# scheme.net
KiCad netlist of a schematic drawn in Altium Designer
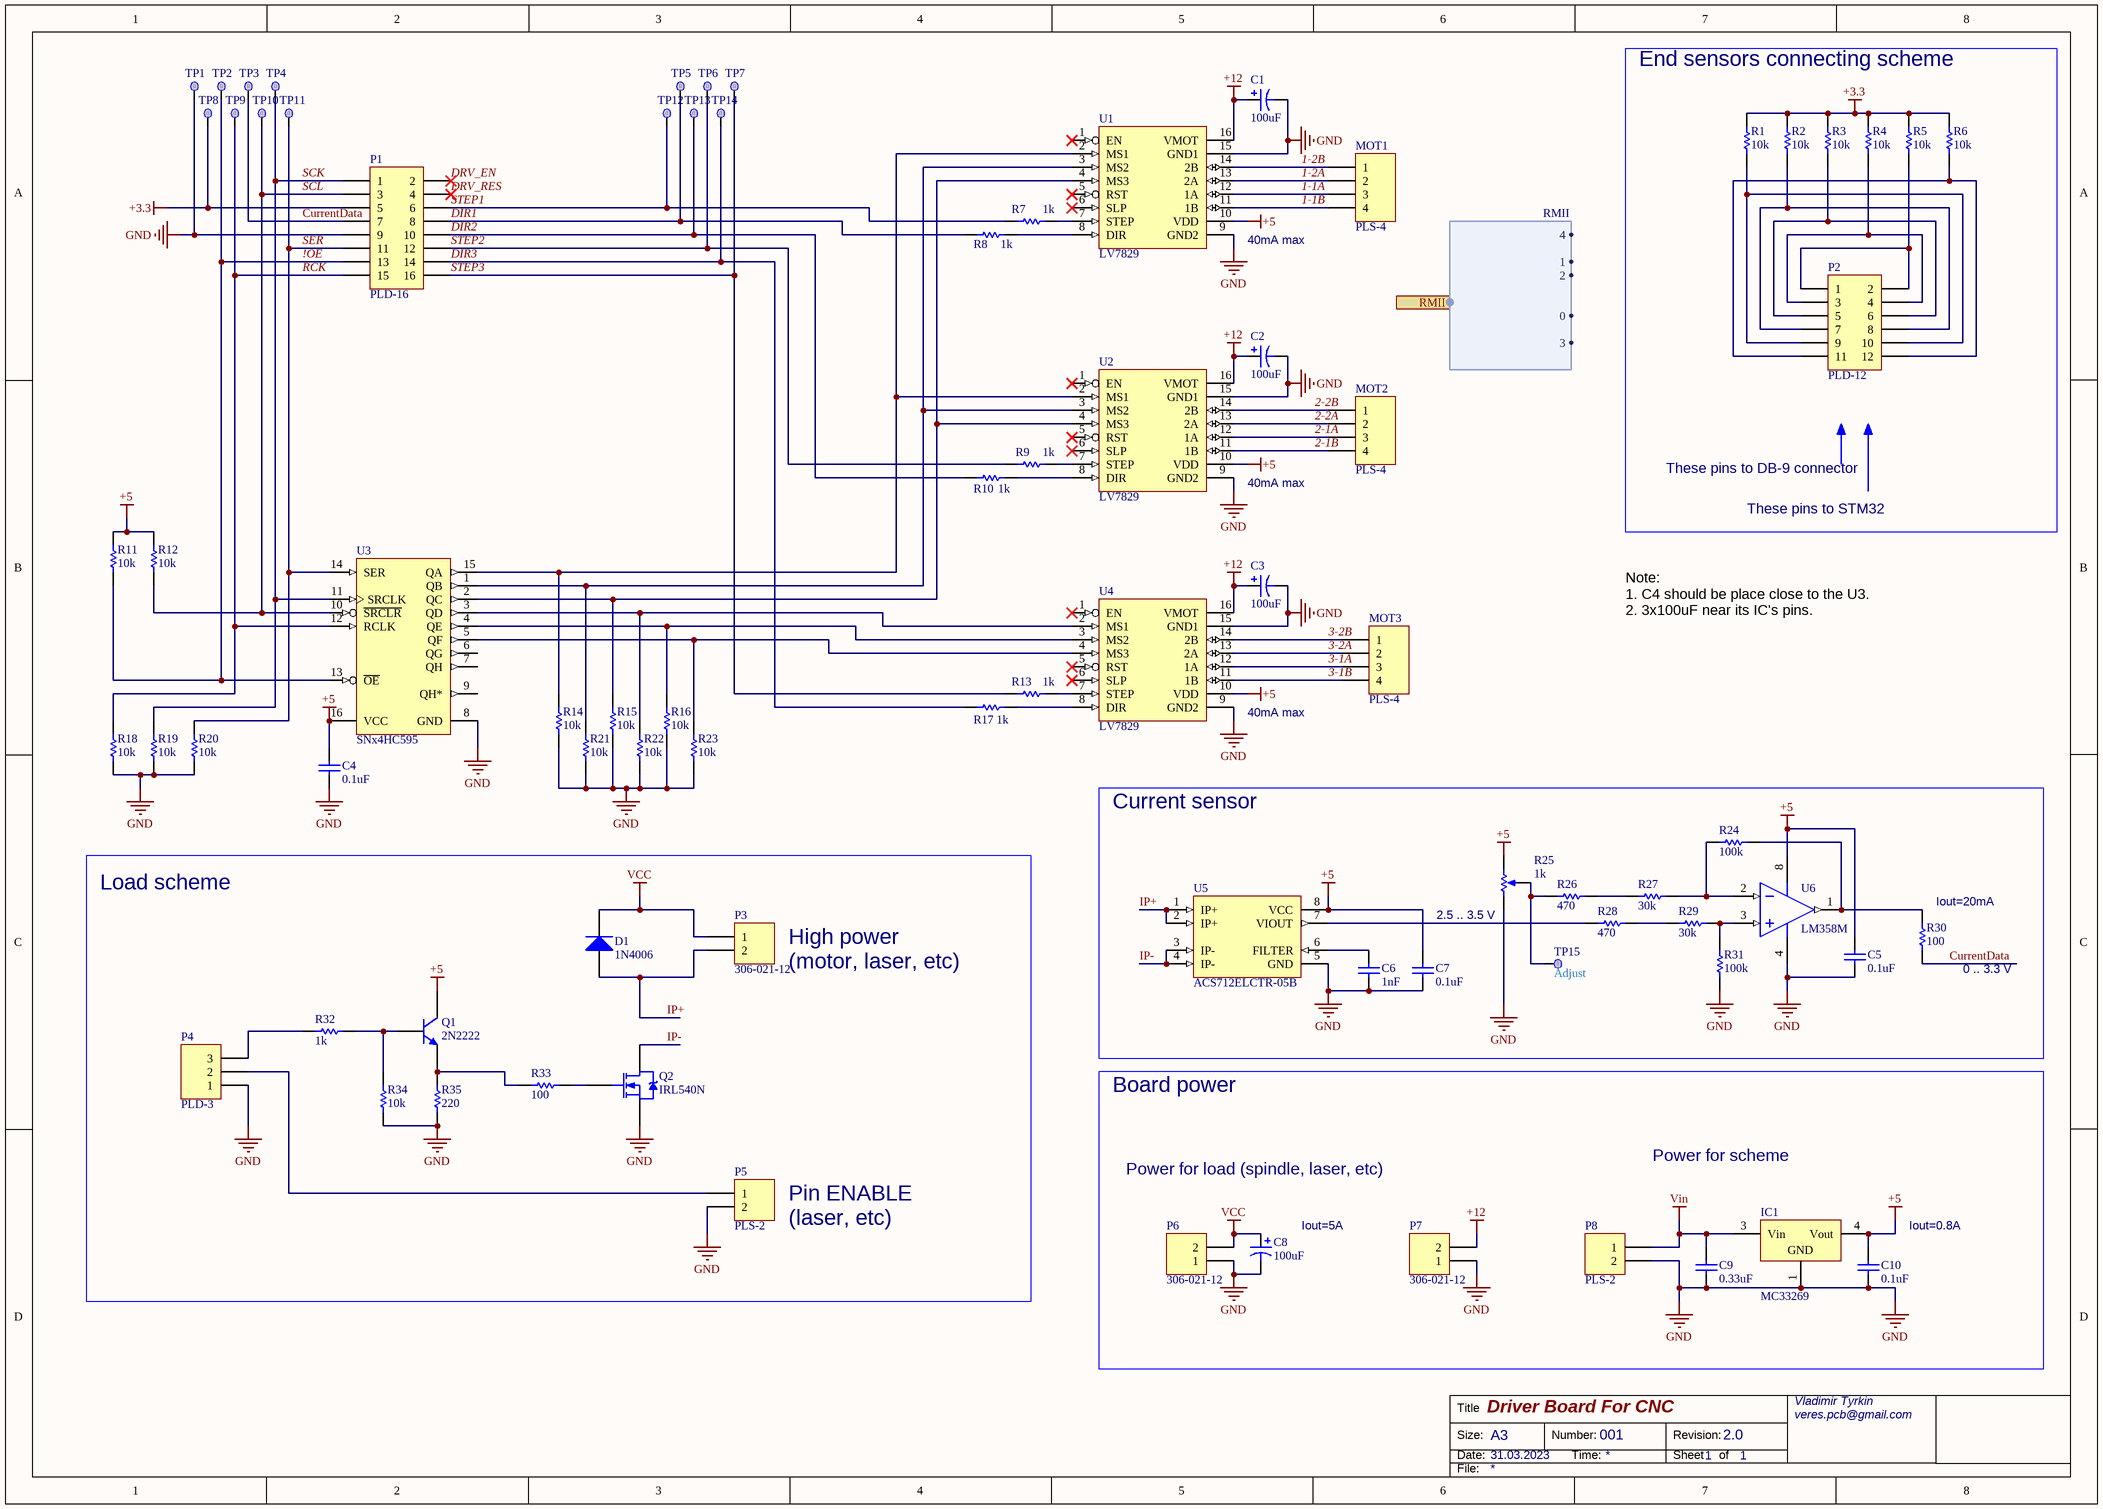
[diagram p0: scheme.SchDoc]

(export (version "E")
  (design (tool "Eeschema 10.0.6"))
  (components
    (comp (ref "C1")
      (value "100uF")
      (footprint "UD-6,3X5,8_NICHICON")
      (description "Polarized Capacitor (Radial) 16V, 105°C, 20% 6.3x5.4mm")
      (fields (field (name "MANUFACTURER") "JB") (field (name "MANUFACTURER_PART_NUMBER") "JCL1C101M063054"))
      (libsource (lib "DriverBoardForCNC") (part "Cap Pol1"))
    )
    (comp (ref "C2")
      (value "100uF")
      (footprint "UD-6,3X5,8_NICHICON")
      (description "Polarized Capacitor (Radial) 16V, 105°C, 20% 6.3x5.4mm")
      (fields (field (name "MANUFACTURER") "JB") (field (name "MANUFACTURER_PART_NUMBER") "JCL1C101M063054"))
      (libsource (lib "DriverBoardForCNC") (part "Cap Pol1"))
    )
    (comp (ref "C3")
      (value "100uF")
      (footprint "UD-6,3X5,8_NICHICON")
      (description "Polarized Capacitor (Radial) 16V, 105°C, 20% 6.3x5.4mm")
      (fields (field (name "MANUFACTURER") "JB") (field (name "MANUFACTURER_PART_NUMBER") "JCL1C101M063054"))
      (libsource (lib "DriverBoardForCNC") (part "Cap Pol1"))
    )
    (comp (ref "C4")
      (value "0.1uF")
      (footprint "C1206")
      (description "Capacitor ceramic SMD")
      (fields
        (field (name "MANUFACTURER") "Murata")
        (field (name "MANUFACTURER_PART_NUMBER") "GRM319R71H104K")
      )
      (libsource (lib "DriverBoardForCNC") (part "Cap"))
    )
    (comp (ref "C5")
      (value "0.1uF")
      (footprint "C1206")
      (description "Capacitor ceramic SMD")
      (fields
        (field (name "MANUFACTURER") "Murata")
        (field (name "MANUFACTURER_PART_NUMBER") "GRM319R71H104K")
      )
      (libsource (lib "DriverBoardForCNC") (part "Cap"))
    )
    (comp (ref "C6")
      (value "1nF")
      (footprint "C0805")
      (description "Capacitor ceramic SMD")
      (fields
        (field (name "MANUFACTURER") "HOLYSTONECAPS")
        (field (name "MANUFACTURER_PART_NUMBER") "MLCC1000pFX7R50V10%0805")
      )
      (libsource (lib "DriverBoardForCNC") (part "Cap"))
    )
    (comp (ref "C7")
      (value "0.1uF")
      (footprint "C1206")
      (description "Capacitor ceramic SMD")
      (fields
        (field (name "MANUFACTURER") "Murata")
        (field (name "MANUFACTURER_PART_NUMBER") "GRM319R71H104K")
      )
      (libsource (lib "DriverBoardForCNC") (part "Cap"))
    )
    (comp (ref "C8")
      (value "100uF")
      (footprint "UD-6,3X5,8_NICHICON")
      (description "Polarized Capacitor (Radial) 16V, 105°C, 20% 6.3x5.4mm")
      (fields (field (name "MANUFACTURER") "JB") (field (name "MANUFACTURER_PART_NUMBER") "JCL1C101M063054"))
      (libsource (lib "DriverBoardForCNC") (part "Cap Pol1"))
    )
    (comp (ref "C9")
      (value "0.33uF")
      (footprint "C1206")
      (description "Capacitor ceramic SMD")
      (fields
        (field (name "MANUFACTURER") "Murata")
        (field (name "MANUFACTURER_PART_NUMBER") "GRM319R71H334KA01D")
      )
      (libsource (lib "DriverBoardForCNC") (part "Cap"))
    )
    (comp (ref "C10")
      (value "0.1uF")
      (footprint "C1206")
      (description "Capacitor ceramic SMD")
      (fields
        (field (name "MANUFACTURER") "Murata")
        (field (name "MANUFACTURER_PART_NUMBER") "GRM319R71H104K")
      )
      (libsource (lib "DriverBoardForCNC") (part "Cap"))
    )
    (comp (ref "D1")
      (value "1N4006")
      (footprint "DO-41")
      (description "1 Amp General Purpose Rectifier")
      (fields (field (name "MANUFACTURER") "DC COMPONENTS CO., LTD."))
      (libsource (lib "DriverBoardForCNC") (part "Diode 1N4004"))
    )
    (comp (ref "IC1")
      (value "MC33269")
      (footprint "DPAK")
      (description "5V Voltage Regulator")
      (fields
        (field (name "MANUFACTURER_PART_NUMBER") "MC33269DT−5.0")
        (field (name "MANUFACTURER") "ON Semiconductor")
      )
      (libsource (lib "DriverBoardForCNC") (part "Volt Reg 5V"))
    )
    (comp (ref "MOT1")
      (value "PLS-4")
      (footprint "HDR1X4")
      (description "Header, 4-Pin")
      (fields
        (field (name "MANUFACTURER") "Connfly")
        (field (name "MANUFACTURER_PART_NUMBER") "DS1021-1*4SF11-B")
      )
      (libsource (lib "DriverBoardForCNC") (part "Header 4"))
    )
    (comp (ref "MOT2")
      (value "PLS-4")
      (footprint "HDR1X4")
      (description "Header, 4-Pin")
      (fields
        (field (name "MANUFACTURER") "Connfly")
        (field (name "MANUFACTURER_PART_NUMBER") "DS1021-1*4SF11-B")
      )
      (libsource (lib "DriverBoardForCNC") (part "Header 4"))
    )
    (comp (ref "MOT3")
      (value "PLS-4")
      (footprint "HDR1X4")
      (description "Header, 4-Pin")
      (fields
        (field (name "MANUFACTURER") "Connfly")
        (field (name "MANUFACTURER_PART_NUMBER") "DS1021-1*4SF11-B")
      )
      (libsource (lib "DriverBoardForCNC") (part "Header 4"))
    )
    (comp (ref "P1")
      (value "PLD-16")
      (footprint "HDR2X8")
      (description "Header, 8-Pin, Dual row")
      (fields
        (field (name "MANUFACTURER") "Connfly")
        (field (name "MANUFACTURER_PART_NUMBER") "DS1021-2*8SF11-B")
      )
      (libsource (lib "DriverBoardForCNC") (part "Header 8X2"))
    )
    (comp (ref "P2")
      (value "PLD-12")
      (footprint "HDR2X6")
      (description "Header, 6-Pin, Dual row")
      (fields
        (field (name "MANUFACTURER") "Connfly")
        (field (name "MANUFACTURER_PART_NUMBER") "DS1021-2*6SF11-B")
      )
      (libsource (lib "DriverBoardForCNC") (part "Header 6X2"))
    )
    (comp (ref "P3")
      (value "306-021-12")
      (footprint "W237-102")
      (description "Screw connector, 2-Pin")
      (fields
        (field (name "MANUFACTURER") "Ningbo Xinya M&E")
        (field (name "MANUFACTURER_PART_NUMBER") "XY306A-5.0-2P-12")
      )
      (libsource (lib "DriverBoardForCNC") (part "Header 2"))
    )
    (comp (ref "P4")
      (value "PLD-3")
      (footprint "HDR1X3")
      (description "Header, 3-Pin")
      (fields
        (field (name "MANUFACTURER") "Connfly")
        (field (name "MANUFACTURER_PART_NUMBER") "DS1021-1*3SF11-B")
      )
      (libsource (lib "DriverBoardForCNC") (part "Header 3"))
    )
    (comp (ref "P5")
      (value "PLS-2")
      (footprint "HDR1X2")
      (description "Header, 2-Pin")
      (fields
        (field (name "MANUFACTURER") "Connfly")
        (field (name "MANUFACTURER_PART_NUMBER") "DS1021-1*2SF11-B")
      )
      (libsource (lib "DriverBoardForCNC") (part "Header 2"))
    )
    (comp (ref "P6")
      (value "306-021-12")
      (footprint "W237-102")
      (description "Screw connector, 2-Pin")
      (fields
        (field (name "MANUFACTURER") "Ningbo Xinya M&E")
        (field (name "MANUFACTURER_PART_NUMBER") "XY306A-5.0-2P-12")
      )
      (libsource (lib "") (part "Header 2_2"))
    )
    (comp (ref "P7")
      (value "306-021-12")
      (footprint "W237-102")
      (description "Screw connector, 2-Pin")
      (fields
        (field (name "MANUFACTURER") "Ningbo Xinya M&E")
        (field (name "MANUFACTURER_PART_NUMBER") "XY306A-5.0-2P-12")
      )
      (libsource (lib "") (part "Header 2_2"))
    )
    (comp (ref "P8")
      (value "PLS-2")
      (footprint "HDR1X2")
      (description "Header, 2-Pin")
      (fields
        (field (name "MANUFACTURER") "Connfly")
        (field (name "MANUFACTURER_PART_NUMBER") "DS1021-1*2SF11-B")
      )
      (libsource (lib "") (part "Header 2_1"))
    )
    (comp (ref "Q1")
      (value "2N2222")
      (footprint "TO92")
      (description "NPN Bipolar Transistor")
      (fields
        (field (name "MANUFACTURER") "ON Semiconductor")
        (field (name "MANUFACTURER_PART_NUMBER") "KSP2222ABU")
      )
      (libsource (lib "DriverBoardForCNC") (part "NPN"))
    )
    (comp (ref "Q2")
      (value "IRL540N")
      (footprint "TO220BV")
      (description "N-Channel Power MOSFET")
      (fields
        (field (name "MANUFACTURER") "Infineon Technologies")
        (field (name "MANUFACTURER_PART_NUMBER") "IRL540NPBF")
      )
      (libsource (lib "DriverBoardForCNC") (part "NMOS-2"))
    )
    (comp (ref "R1")
      (value "10k")
      (footprint "RES-0805")
      (description "Rectangular Thick Film Chip Resistor")
      (fields
        (field (name "MANUFACTURER_PART_NUMBER") "RC0805FR-0710KL")
        (field (name "MANUFACTURER") "Yageo")
      )
      (libsource (lib "DriverBoardForCNC") (part "Res"))
    )
    (comp (ref "R2")
      (value "10k")
      (footprint "RES-0805")
      (description "Rectangular Thick Film Chip Resistor")
      (fields
        (field (name "MANUFACTURER_PART_NUMBER") "RC0805FR-0710KL")
        (field (name "MANUFACTURER") "Yageo")
      )
      (libsource (lib "DriverBoardForCNC") (part "Res"))
    )
    (comp (ref "R3")
      (value "10k")
      (footprint "RES-0805")
      (description "Rectangular Thick Film Chip Resistor")
      (fields
        (field (name "MANUFACTURER_PART_NUMBER") "RC0805FR-0710KL")
        (field (name "MANUFACTURER") "Yageo")
      )
      (libsource (lib "DriverBoardForCNC") (part "Res"))
    )
    (comp (ref "R4")
      (value "10k")
      (footprint "RES-0805")
      (description "Rectangular Thick Film Chip Resistor")
      (fields
        (field (name "MANUFACTURER_PART_NUMBER") "RC0805FR-0710KL")
        (field (name "MANUFACTURER") "Yageo")
      )
      (libsource (lib "DriverBoardForCNC") (part "Res"))
    )
    (comp (ref "R5")
      (value "10k")
      (footprint "RES-0805")
      (description "Rectangular Thick Film Chip Resistor")
      (fields
        (field (name "MANUFACTURER_PART_NUMBER") "RC0805FR-0710KL")
        (field (name "MANUFACTURER") "Yageo")
      )
      (libsource (lib "DriverBoardForCNC") (part "Res"))
    )
    (comp (ref "R6")
      (value "10k")
      (footprint "RES-0805")
      (description "Rectangular Thick Film Chip Resistor")
      (fields
        (field (name "MANUFACTURER_PART_NUMBER") "RC0805FR-0710KL")
        (field (name "MANUFACTURER") "Yageo")
      )
      (libsource (lib "DriverBoardForCNC") (part "Res"))
    )
    (comp (ref "R7")
      (value "1k")
      (footprint "RES-0805")
      (description "Rectangular Thick Film Chip Resistor")
      (fields
        (field (name "MANUFACTURER") "Yageo")
        (field (name "MANUFACTURER_PART_NUMBER") "RC0805FR-071KL")
      )
      (libsource (lib "DriverBoardForCNC") (part "Res"))
    )
    (comp (ref "R8")
      (value "1k")
      (footprint "RES-0805")
      (description "Rectangular Thick Film Chip Resistor")
      (fields
        (field (name "MANUFACTURER") "Yageo")
        (field (name "MANUFACTURER_PART_NUMBER") "RC0805FR-071KL")
      )
      (libsource (lib "DriverBoardForCNC") (part "Res"))
    )
    (comp (ref "R9")
      (value "1k")
      (footprint "RES-0805")
      (description "Rectangular Thick Film Chip Resistor")
      (fields
        (field (name "MANUFACTURER") "Yageo")
        (field (name "MANUFACTURER_PART_NUMBER") "RC0805FR-071KL")
      )
      (libsource (lib "DriverBoardForCNC") (part "Res"))
    )
    (comp (ref "R10")
      (value "1k")
      (footprint "RES-0805")
      (description "Rectangular Thick Film Chip Resistor")
      (fields
        (field (name "MANUFACTURER") "Yageo")
        (field (name "MANUFACTURER_PART_NUMBER") "RC0805FR-071KL")
      )
      (libsource (lib "DriverBoardForCNC") (part "Res"))
    )
    (comp (ref "R11")
      (value "10k")
      (footprint "RES-0805")
      (description "Rectangular Thick Film Chip Resistor")
      (fields
        (field (name "MANUFACTURER_PART_NUMBER") "RC0805FR-0710KL")
        (field (name "MANUFACTURER") "Yageo")
      )
      (libsource (lib "DriverBoardForCNC") (part "Res"))
    )
    (comp (ref "R12")
      (value "10k")
      (footprint "RES-0805")
      (description "Rectangular Thick Film Chip Resistor")
      (fields
        (field (name "MANUFACTURER_PART_NUMBER") "RC0805FR-0710KL")
        (field (name "MANUFACTURER") "Yageo")
      )
      (libsource (lib "DriverBoardForCNC") (part "Res"))
    )
    (comp (ref "R13")
      (value "1k")
      (footprint "RES-0805")
      (description "Rectangular Thick Film Chip Resistor")
      (fields
        (field (name "MANUFACTURER") "Yageo")
        (field (name "MANUFACTURER_PART_NUMBER") "RC0805FR-071KL")
      )
      (libsource (lib "DriverBoardForCNC") (part "Res"))
    )
    (comp (ref "R14")
      (value "10k")
      (footprint "RES-0805")
      (description "Rectangular Thick Film Chip Resistor")
      (fields
        (field (name "MANUFACTURER_PART_NUMBER") "RC0805FR-0710KL")
        (field (name "MANUFACTURER") "Yageo")
      )
      (libsource (lib "DriverBoardForCNC") (part "Res"))
    )
    (comp (ref "R15")
      (value "10k")
      (footprint "RES-0805")
      (description "Rectangular Thick Film Chip Resistor")
      (fields
        (field (name "MANUFACTURER_PART_NUMBER") "RC0805FR-0710KL")
        (field (name "MANUFACTURER") "Yageo")
      )
      (libsource (lib "DriverBoardForCNC") (part "Res"))
    )
    (comp (ref "R16")
      (value "10k")
      (footprint "RES-0805")
      (description "Rectangular Thick Film Chip Resistor")
      (fields
        (field (name "MANUFACTURER_PART_NUMBER") "RC0805FR-0710KL")
        (field (name "MANUFACTURER") "Yageo")
      )
      (libsource (lib "DriverBoardForCNC") (part "Res"))
    )
    (comp (ref "R17")
      (value "1k")
      (footprint "RES-0805")
      (description "Rectangular Thick Film Chip Resistor")
      (fields
        (field (name "MANUFACTURER") "Yageo")
        (field (name "MANUFACTURER_PART_NUMBER") "RC0805FR-071KL")
      )
      (libsource (lib "DriverBoardForCNC") (part "Res"))
    )
    (comp (ref "R18")
      (value "10k")
      (footprint "RES-0805")
      (description "Rectangular Thick Film Chip Resistor")
      (fields
        (field (name "MANUFACTURER_PART_NUMBER") "RC0805FR-0710KL")
        (field (name "MANUFACTURER") "Yageo")
      )
      (libsource (lib "DriverBoardForCNC") (part "Res"))
    )
    (comp (ref "R19")
      (value "10k")
      (footprint "RES-0805")
      (description "Rectangular Thick Film Chip Resistor")
      (fields
        (field (name "MANUFACTURER_PART_NUMBER") "RC0805FR-0710KL")
        (field (name "MANUFACTURER") "Yageo")
      )
      (libsource (lib "DriverBoardForCNC") (part "Res"))
    )
    (comp (ref "R20")
      (value "10k")
      (footprint "RES-0805")
      (description "Rectangular Thick Film Chip Resistor")
      (fields
        (field (name "MANUFACTURER_PART_NUMBER") "RC0805FR-0710KL")
        (field (name "MANUFACTURER") "Yageo")
      )
      (libsource (lib "DriverBoardForCNC") (part "Res"))
    )
    (comp (ref "R21")
      (value "10k")
      (footprint "RES-0805")
      (description "Rectangular Thick Film Chip Resistor")
      (fields
        (field (name "MANUFACTURER_PART_NUMBER") "RC0805FR-0710KL")
        (field (name "MANUFACTURER") "Yageo")
      )
      (libsource (lib "DriverBoardForCNC") (part "Res"))
    )
    (comp (ref "R22")
      (value "10k")
      (footprint "RES-0805")
      (description "Rectangular Thick Film Chip Resistor")
      (fields
        (field (name "MANUFACTURER_PART_NUMBER") "RC0805FR-0710KL")
        (field (name "MANUFACTURER") "Yageo")
      )
      (libsource (lib "DriverBoardForCNC") (part "Res"))
    )
    (comp (ref "R23")
      (value "10k")
      (footprint "RES-0805")
      (description "Rectangular Thick Film Chip Resistor")
      (fields
        (field (name "MANUFACTURER_PART_NUMBER") "RC0805FR-0710KL")
        (field (name "MANUFACTURER") "Yageo")
      )
      (libsource (lib "DriverBoardForCNC") (part "Res"))
    )
    (comp (ref "R24")
      (value "100k")
      (footprint "RES-0805")
      (description "Rectangular Thick Film Chip Resistor")
      (fields
        (field (name "MANUFACTURER_PART_NUMBER") "RC0805FR-07100KL")
        (field (name "MANUFACTURER") "Yageo")
      )
      (libsource (lib "DriverBoardForCNC") (part "Res"))
    )
    (comp (ref "R25")
      (value "1k")
      (footprint "VR5")
      (description "Potentiometer")
      (fields
        (field (name "MANUFACTURER_PART_NUMBER") "3296W-1-102LF")
        (field (name "MANUFACTURER") "Bourns")
      )
      (libsource (lib "DriverBoardForCNC") (part "RPot"))
    )
    (comp (ref "R26")
      (value "470")
      (footprint "RES-0805")
      (description "Rectangular Thick Film Chip Resistor")
      (fields
        (field (name "MANUFACTURER_PART_NUMBER") "RC0805FR-07470RL")
        (field (name "MANUFACTURER") "Yageo")
      )
      (libsource (lib "DriverBoardForCNC") (part "Res"))
    )
    (comp (ref "R27")
      (value "30k")
      (footprint "RES-0805")
      (description "Rectangular Thick Film Chip Resistor")
      (fields
        (field (name "MANUFACTURER_PART_NUMBER") "RC0805FR-0730KL")
        (field (name "MANUFACTURER") "Yageo")
      )
      (libsource (lib "DriverBoardForCNC") (part "Res"))
    )
    (comp (ref "R28")
      (value "470")
      (footprint "RES-1206")
      (description "Rectangular Thick Film Chip Resistor")
      (fields
        (field (name "MANUFACTURER_PART_NUMBER") "RC1206FR-07470RL")
        (field (name "MANUFACTURER") "Yageo")
      )
      (libsource (lib "DriverBoardForCNC") (part "Res"))
    )
    (comp (ref "R29")
      (value "30k")
      (footprint "RES-0805")
      (description "Rectangular Thick Film Chip Resistor")
      (fields
        (field (name "MANUFACTURER_PART_NUMBER") "RC0805FR-0730KL")
        (field (name "MANUFACTURER") "Yageo")
      )
      (libsource (lib "DriverBoardForCNC") (part "Res"))
    )
    (comp (ref "R30")
      (value "100")
      (footprint "RES-0805")
      (description "Rectangular Thick Film Chip Resistor")
      (fields
        (field (name "MANUFACTURER_PART_NUMBER") "RC0805FR-07100RL")
        (field (name "MANUFACTURER") "Yageo")
      )
      (libsource (lib "DriverBoardForCNC") (part "Res"))
    )
    (comp (ref "R31")
      (value "100k")
      (footprint "RES-0805")
      (description "Rectangular Thick Film Chip Resistor")
      (fields
        (field (name "MANUFACTURER_PART_NUMBER") "RC0805FR-07100KL")
        (field (name "MANUFACTURER") "Yageo")
      )
      (libsource (lib "DriverBoardForCNC") (part "Res"))
    )
    (comp (ref "R32")
      (value "1k")
      (footprint "RES-0805")
      (description "Rectangular Thick Film Chip Resistor")
      (fields
        (field (name "MANUFACTURER") "Yageo")
        (field (name "MANUFACTURER_PART_NUMBER") "RC0805FR-071KL")
      )
      (libsource (lib "DriverBoardForCNC") (part "Res"))
    )
    (comp (ref "R33")
      (value "100")
      (footprint "RES-0805")
      (description "Rectangular Thick Film Chip Resistor")
      (fields
        (field (name "MANUFACTURER_PART_NUMBER") "RC0805FR-07100RL")
        (field (name "MANUFACTURER") "Yageo")
      )
      (libsource (lib "DriverBoardForCNC") (part "Res"))
    )
    (comp (ref "R34")
      (value "10k")
      (footprint "RES-0805")
      (description "Rectangular Thick Film Chip Resistor")
      (fields
        (field (name "MANUFACTURER_PART_NUMBER") "RC0805FR-0710KL")
        (field (name "MANUFACTURER") "Yageo")
      )
      (libsource (lib "DriverBoardForCNC") (part "Res"))
    )
    (comp (ref "R35")
      (value "220")
      (footprint "RES-0805")
      (description "Rectangular Thick Film Chip Resistor")
      (fields
        (field (name "MANUFACTURER_PART_NUMBER") "RC0805FR-07220RL")
        (field (name "MANUFACTURER") "Yageo")
      )
      (libsource (lib "DriverBoardForCNC") (part "Res"))
    )
    (comp (ref "TP1")
      (value "~")
      (footprint "TP_SMD_1MM")
      (description "Test Point")
      (fields (field (name "MANUFACTURER_PART_NUMBER") "n/a"))
      (libsource (lib "DriverBoardForCNC") (part "Test Point"))
    )
    (comp (ref "TP2")
      (value "~")
      (footprint "TP_SMD_1MM")
      (description "Test Point")
      (fields (field (name "MANUFACTURER_PART_NUMBER") "n/a"))
      (libsource (lib "DriverBoardForCNC") (part "Test Point"))
    )
    (comp (ref "TP3")
      (value "~")
      (footprint "TP_SMD_1MM")
      (description "Test Point")
      (fields (field (name "MANUFACTURER_PART_NUMBER") "n/a"))
      (libsource (lib "DriverBoardForCNC") (part "Test Point"))
    )
    (comp (ref "TP4")
      (value "~")
      (footprint "TP_SMD_1MM")
      (description "Test Point")
      (fields (field (name "MANUFACTURER_PART_NUMBER") "n/a"))
      (libsource (lib "DriverBoardForCNC") (part "Test Point"))
    )
    (comp (ref "TP5")
      (value "~")
      (footprint "TP_SMD_1MM")
      (description "Test Point")
      (fields (field (name "MANUFACTURER_PART_NUMBER") "n/a"))
      (libsource (lib "DriverBoardForCNC") (part "Test Point"))
    )
    (comp (ref "TP6")
      (value "~")
      (footprint "TP_SMD_1MM")
      (description "Test Point")
      (fields (field (name "MANUFACTURER_PART_NUMBER") "n/a"))
      (libsource (lib "DriverBoardForCNC") (part "Test Point"))
    )
    (comp (ref "TP7")
      (value "~")
      (footprint "TP_SMD_1MM")
      (description "Test Point")
      (fields (field (name "MANUFACTURER_PART_NUMBER") "n/a"))
      (libsource (lib "DriverBoardForCNC") (part "Test Point"))
    )
    (comp (ref "TP8")
      (value "~")
      (footprint "TP_SMD_1MM")
      (description "Test Point")
      (fields (field (name "MANUFACTURER_PART_NUMBER") "n/a"))
      (libsource (lib "DriverBoardForCNC") (part "Test Point"))
    )
    (comp (ref "TP9")
      (value "~")
      (footprint "TP_SMD_1MM")
      (description "Test Point")
      (fields (field (name "MANUFACTURER_PART_NUMBER") "n/a"))
      (libsource (lib "DriverBoardForCNC") (part "Test Point"))
    )
    (comp (ref "TP10")
      (value "~")
      (footprint "TP_SMD_1MM")
      (description "Test Point")
      (fields (field (name "MANUFACTURER_PART_NUMBER") "n/a"))
      (libsource (lib "DriverBoardForCNC") (part "Test Point"))
    )
    (comp (ref "TP11")
      (value "~")
      (footprint "TP_SMD_1MM")
      (description "Test Point")
      (fields (field (name "MANUFACTURER_PART_NUMBER") "n/a"))
      (libsource (lib "DriverBoardForCNC") (part "Test Point"))
    )
    (comp (ref "TP12")
      (value "~")
      (footprint "TP_SMD_1MM")
      (description "Test Point")
      (fields (field (name "MANUFACTURER_PART_NUMBER") "n/a"))
      (libsource (lib "DriverBoardForCNC") (part "Test Point"))
    )
    (comp (ref "TP13")
      (value "~")
      (footprint "TP_SMD_1MM")
      (description "Test Point")
      (fields (field (name "MANUFACTURER_PART_NUMBER") "n/a"))
      (libsource (lib "DriverBoardForCNC") (part "Test Point"))
    )
    (comp (ref "TP14")
      (value "~")
      (footprint "TP_SMD_1MM")
      (description "Test Point")
      (fields (field (name "MANUFACTURER_PART_NUMBER") "n/a"))
      (libsource (lib "DriverBoardForCNC") (part "Test Point"))
    )
    (comp (ref "TP15")
      (value "Adjust")
      (footprint "TestPoint")
      (description "Test Point")
      (fields (field (name "MANUFACTURER_PART_NUMBER") "n/a"))
      (libsource (lib "") (part "Test Point_1"))
    )
    (comp (ref "U1")
      (value "LV7829")
      (footprint "LV8729_BREAKOUT")
      (description "Stepper motor driver")
      (fields (field (name "MANUFACTURER_PART_NUMBER") "LV7829 Module") (field (name "MANUFACTURER") "China"))
      (libsource (lib "DriverBoardForCNC") (part "LV7829"))
    )
    (comp (ref "U2")
      (value "LV7829")
      (footprint "LV8729_BREAKOUT")
      (description "Stepper motor driver")
      (fields (field (name "MANUFACTURER_PART_NUMBER") "LV7829 Module") (field (name "MANUFACTURER") "China"))
      (libsource (lib "DriverBoardForCNC") (part "LV7829"))
    )
    (comp (ref "U3")
      (value "SNx4HC595")
      (footprint "SO16")
      (description "8-bit shift register with 3-state output register")
      (fields (field (name "MANUFACTURER_PART_NUMBER") "SN74HC595D") (field (name "MANUFACTURER") "TI"))
      (libsource (lib "DriverBoardForCNC") (part "SNx4HC595"))
    )
    (comp (ref "U4")
      (value "LV7829")
      (footprint "LV8729_BREAKOUT")
      (description "Stepper motor driver")
      (fields (field (name "MANUFACTURER_PART_NUMBER") "LV7829 Module") (field (name "MANUFACTURER") "China"))
      (libsource (lib "DriverBoardForCNC") (part "LV7829"))
    )
    (comp (ref "U5")
      (value "ACS712ELCTR-05B")
      (footprint "SO-8_L")
      (description "Hall-Effect-Based Linear Current Sensor +-5A")
      (fields (field (name "MANUFACTURER") "Allegro") (field (name "Comment") "Current Sensor"))
      (libsource (lib "DriverBoardForCNC") (part "ACS712ELCTR-05B"))
    )
    (comp (ref "U6")
      (value "LM358M")
      (footprint "SO-8_L")
      (description "FET Operational Amplifier")
      (fields (field (name "MANUFACTURER_PART_NUMBER") "LM358M/NOPB") (field (name "MANUFACTURER") "TI"))
      (libsource (lib "DriverBoardForCNC") (part "Op Amp"))
    )
  )
  (nets
    (net (code "2") (name "+3.3") (class "Default")
      (node (ref "P1") (pin "5") (pinfunction "5_5") (pintype "passive"))
      (node (ref "R1") (pin "1") (pinfunction "1_1") (pintype "passive"))
      (node (ref "R2") (pin "1") (pinfunction "1_1") (pintype "passive"))
      (node (ref "R3") (pin "1") (pinfunction "1_1") (pintype "passive"))
      (node (ref "R4") (pin "1") (pinfunction "1_1") (pintype "passive"))
      (node (ref "R5") (pin "1") (pinfunction "1_1") (pintype "passive"))
      (node (ref "R6") (pin "1") (pinfunction "1_1") (pintype "passive"))
      (node (ref "TP8") (pin "1") (pinfunction "1_1") (pintype "passive"))
    )
    (net (code "3") (name "+5") (class "Default")
      (node (ref "C10") (pin "2") (pinfunction "2_2") (pintype "passive"))
      (node (ref "C4") (pin "2") (pinfunction "2_2") (pintype "passive"))
      (node (ref "C5") (pin "1") (pinfunction "1_1") (pintype "passive"))
      (node (ref "C7") (pin "2") (pinfunction "2_2") (pintype "passive"))
      (node (ref "IC1") (pin "4") (pinfunction "Vout_4") (pintype "passive"))
      (node (ref "Q1") (pin "1") (pinfunction "C_1") (pintype "passive"))
      (node (ref "R11") (pin "1") (pinfunction "1_1") (pintype "passive"))
      (node (ref "R12") (pin "1") (pinfunction "1_1") (pintype "passive"))
      (node (ref "R25") (pin "3") (pinfunction "BOT_3") (pintype "passive"))
      (node (ref "U1") (pin "10") (pinfunction "VDD_10") (pintype "power_in"))
      (node (ref "U2") (pin "10") (pinfunction "VDD_10") (pintype "power_in"))
      (node (ref "U3") (pin "16") (pinfunction "VCC_16") (pintype "power_in"))
      (node (ref "U4") (pin "10") (pinfunction "VDD_10") (pintype "power_in"))
      (node (ref "U5") (pin "8") (pinfunction "VCC_8") (pintype "power_in"))
      (node (ref "U6") (pin "8") (pinfunction "V+_8") (pintype "power_in"))
    )
    (net (code "4") (name "+12") (class "Default")
      (node (ref "C1") (pin "1") (pinfunction "1_1") (pintype "passive"))
      (node (ref "C2") (pin "1") (pinfunction "1_1") (pintype "passive"))
      (node (ref "C3") (pin "1") (pinfunction "1_1") (pintype "passive"))
      (node (ref "P7") (pin "2") (pinfunction "2_2") (pintype "passive"))
      (node (ref "U1") (pin "16") (pinfunction "VMOT_16") (pintype "power_in"))
      (node (ref "U2") (pin "16") (pinfunction "VMOT_16") (pintype "power_in"))
      (node (ref "U4") (pin "16") (pinfunction "VMOT_16") (pintype "power_in"))
    )
    (net (code "5") (name "/!OE") (class "Default")
      (node (ref "P1") (pin "13") (pinfunction "13_13") (pintype "passive"))
      (node (ref "R11") (pin "2") (pinfunction "2_2") (pintype "passive"))
      (node (ref "TP2") (pin "1") (pinfunction "1_1") (pintype "passive"))
      (node (ref "U3") (pin "13") (pinfunction "~{OE}_13") (pintype "input"))
    )
    (net (code "6") (name "/1-1A") (class "Default")
      (node (ref "MOT1") (pin "3") (pinfunction "3_3") (pintype "passive"))
      (node (ref "U1") (pin "12") (pinfunction "1A_12") (pintype "bidirectional"))
    )
    (net (code "7") (name "/1-1B") (class "Default")
      (node (ref "MOT1") (pin "4") (pinfunction "4_4") (pintype "passive"))
      (node (ref "U1") (pin "11") (pinfunction "1B_11") (pintype "bidirectional"))
    )
    (net (code "8") (name "/1-2A") (class "Default")
      (node (ref "MOT1") (pin "2") (pinfunction "2_2") (pintype "passive"))
      (node (ref "U1") (pin "13") (pinfunction "2A_13") (pintype "bidirectional"))
    )
    (net (code "9") (name "/1-2B") (class "Default")
      (node (ref "MOT1") (pin "1") (pinfunction "1_1") (pintype "passive"))
      (node (ref "U1") (pin "14") (pinfunction "2B_14") (pintype "bidirectional"))
    )
    (net (code "10") (name "/2-1A") (class "Default")
      (node (ref "MOT2") (pin "3") (pinfunction "3_3") (pintype "passive"))
      (node (ref "U2") (pin "12") (pinfunction "1A_12") (pintype "bidirectional"))
    )
    (net (code "11") (name "/2-1B") (class "Default")
      (node (ref "MOT2") (pin "4") (pinfunction "4_4") (pintype "passive"))
      (node (ref "U2") (pin "11") (pinfunction "1B_11") (pintype "bidirectional"))
    )
    (net (code "12") (name "/2-2A") (class "Default")
      (node (ref "MOT2") (pin "2") (pinfunction "2_2") (pintype "passive"))
      (node (ref "U2") (pin "13") (pinfunction "2A_13") (pintype "bidirectional"))
    )
    (net (code "13") (name "/2-2B") (class "Default")
      (node (ref "MOT2") (pin "1") (pinfunction "1_1") (pintype "passive"))
      (node (ref "U2") (pin "14") (pinfunction "2B_14") (pintype "bidirectional"))
    )
    (net (code "14") (name "/3-1A") (class "Default")
      (node (ref "MOT3") (pin "3") (pinfunction "3_3") (pintype "passive"))
      (node (ref "U4") (pin "12") (pinfunction "1A_12") (pintype "bidirectional"))
    )
    (net (code "15") (name "/3-1B") (class "Default")
      (node (ref "MOT3") (pin "4") (pinfunction "4_4") (pintype "passive"))
      (node (ref "U4") (pin "11") (pinfunction "1B_11") (pintype "bidirectional"))
    )
    (net (code "16") (name "/3-2A") (class "Default")
      (node (ref "MOT3") (pin "2") (pinfunction "2_2") (pintype "passive"))
      (node (ref "U4") (pin "13") (pinfunction "2A_13") (pintype "bidirectional"))
    )
    (net (code "17") (name "/3-2B") (class "Default")
      (node (ref "MOT3") (pin "1") (pinfunction "1_1") (pintype "passive"))
      (node (ref "U4") (pin "14") (pinfunction "2B_14") (pintype "bidirectional"))
    )
    (net (code "18") (name "/CurrentData") (class "Default")
      (node (ref "P1") (pin "7") (pinfunction "7_7") (pintype "passive"))
      (node (ref "R30") (pin "2") (pinfunction "2_2") (pintype "passive"))
      (node (ref "TP3") (pin "1") (pinfunction "1_1") (pintype "passive"))
    )
    (net (code "19") (name "/DIR1") (class "Default")
      (node (ref "P1") (pin "8") (pinfunction "8_8") (pintype "passive"))
      (node (ref "R8") (pin "2") (pinfunction "2_2") (pintype "passive"))
      (node (ref "TP5") (pin "1") (pinfunction "1_1") (pintype "passive"))
    )
    (net (code "20") (name "/DIR2") (class "Default")
      (node (ref "P1") (pin "10") (pinfunction "10_10") (pintype "passive"))
      (node (ref "R10") (pin "2") (pinfunction "2_2") (pintype "passive"))
      (node (ref "TP13") (pin "1") (pinfunction "1_1") (pintype "passive"))
    )
    (net (code "21") (name "/DIR3") (class "Default")
      (node (ref "P1") (pin "14") (pinfunction "14_14") (pintype "passive"))
      (node (ref "R17") (pin "2") (pinfunction "2_2") (pintype "passive"))
      (node (ref "TP14") (pin "1") (pinfunction "1_1") (pintype "passive"))
    )
    (net (code "22") (name "/DRV_EN") (class "Default")
      (node (ref "P1") (pin "2") (pinfunction "2_2") (pintype "passive+no_connect"))
    )
    (net (code "23") (name "/DRV_RES") (class "Default")
      (node (ref "P1") (pin "4") (pinfunction "4_4") (pintype "passive+no_connect"))
    )
    (net (code "24") (name "/IP+") (class "Default")
      (node (ref "D1") (pin "1") (pinfunction "A_1") (pintype "passive"))
      (node (ref "P3") (pin "2") (pinfunction "2_2") (pintype "passive"))
      (node (ref "U5") (pin "1") (pinfunction "IP+_1") (pintype "input"))
      (node (ref "U5") (pin "2") (pinfunction "IP+_2") (pintype "input"))
    )
    (net (code "25") (name "/IP-") (class "Default")
      (node (ref "Q2") (pin "2") (pinfunction "D_2") (pintype "passive"))
      (node (ref "U5") (pin "3") (pinfunction "IP-_3") (pintype "input"))
      (node (ref "U5") (pin "4") (pinfunction "IP-_4") (pintype "input"))
    )
    (net (code "26") (name "/RCK") (class "Default")
      (node (ref "P1") (pin "15") (pinfunction "15_15") (pintype "passive"))
      (node (ref "R18") (pin "1") (pinfunction "1_1") (pintype "passive"))
      (node (ref "TP9") (pin "1") (pinfunction "1_1") (pintype "passive"))
      (node (ref "U3") (pin "12") (pinfunction "RCLK_12") (pintype "input"))
    )
    (net (code "27") (name "/SCK") (class "Default")
      (node (ref "P1") (pin "1") (pinfunction "1_1") (pintype "passive"))
      (node (ref "R19") (pin "1") (pinfunction "1_1") (pintype "passive"))
      (node (ref "TP4") (pin "1") (pinfunction "1_1") (pintype "passive"))
      (node (ref "U3") (pin "11") (pinfunction "SRCLK_11") (pintype "input"))
    )
    (net (code "28") (name "/SCL") (class "Default")
      (node (ref "P1") (pin "3") (pinfunction "3_3") (pintype "passive"))
      (node (ref "R12") (pin "2") (pinfunction "2_2") (pintype "passive"))
      (node (ref "TP10") (pin "1") (pinfunction "1_1") (pintype "passive"))
      (node (ref "U3") (pin "10") (pinfunction "~{SRCLR}_10") (pintype "input"))
    )
    (net (code "29") (name "/SER") (class "Default")
      (node (ref "P1") (pin "11") (pinfunction "11_11") (pintype "passive"))
      (node (ref "R20") (pin "1") (pinfunction "1_1") (pintype "passive"))
      (node (ref "TP11") (pin "1") (pinfunction "1_1") (pintype "passive"))
      (node (ref "U3") (pin "14") (pinfunction "SER_14") (pintype "input"))
    )
    (net (code "30") (name "/STEP1") (class "Default")
      (node (ref "P1") (pin "6") (pinfunction "6_6") (pintype "passive"))
      (node (ref "R7") (pin "2") (pinfunction "2_2") (pintype "passive"))
      (node (ref "TP12") (pin "1") (pinfunction "1_1") (pintype "passive"))
    )
    (net (code "31") (name "/STEP2") (class "Default")
      (node (ref "P1") (pin "12") (pinfunction "12_12") (pintype "passive"))
      (node (ref "R9") (pin "2") (pinfunction "2_2") (pintype "passive"))
      (node (ref "TP6") (pin "1") (pinfunction "1_1") (pintype "passive"))
    )
    (net (code "32") (name "/STEP3") (class "Default")
      (node (ref "P1") (pin "16") (pinfunction "16_16") (pintype "passive"))
      (node (ref "R13") (pin "2") (pinfunction "2_2") (pintype "passive"))
      (node (ref "TP7") (pin "1") (pinfunction "1_1") (pintype "passive"))
    )
    (net (code "34") (name "GND") (class "Default")
      (node (ref "C1") (pin "2") (pinfunction "2_2") (pintype "passive"))
      (node (ref "C10") (pin "1") (pinfunction "1_1") (pintype "passive"))
      (node (ref "C2") (pin "2") (pinfunction "2_2") (pintype "passive"))
      (node (ref "C3") (pin "2") (pinfunction "2_2") (pintype "passive"))
      (node (ref "C4") (pin "1") (pinfunction "1_1") (pintype "passive"))
      (node (ref "C5") (pin "2") (pinfunction "2_2") (pintype "passive"))
      (node (ref "C6") (pin "1") (pinfunction "1_1") (pintype "passive"))
      (node (ref "C7") (pin "1") (pinfunction "1_1") (pintype "passive"))
      (node (ref "C8") (pin "2") (pinfunction "2_2") (pintype "passive"))
      (node (ref "C9") (pin "1") (pinfunction "1_1") (pintype "passive"))
      (node (ref "IC1") (pin "1") (pinfunction "GND_1") (pintype "passive"))
      (node (ref "P1") (pin "9") (pinfunction "9_9") (pintype "passive"))
      (node (ref "P4") (pin "1") (pinfunction "1_1") (pintype "passive"))
      (node (ref "P5") (pin "2") (pinfunction "2_2") (pintype "passive"))
      (node (ref "P6") (pin "1") (pinfunction "1_1") (pintype "passive"))
      (node (ref "P7") (pin "1") (pinfunction "1_1") (pintype "passive"))
      (node (ref "P8") (pin "2") (pinfunction "2_2") (pintype "passive"))
      (node (ref "Q2") (pin "3") (pinfunction "S_3") (pintype "passive"))
      (node (ref "R14") (pin "2") (pinfunction "2_2") (pintype "passive"))
      (node (ref "R15") (pin "2") (pinfunction "2_2") (pintype "passive"))
      (node (ref "R16") (pin "2") (pinfunction "2_2") (pintype "passive"))
      (node (ref "R18") (pin "2") (pinfunction "2_2") (pintype "passive"))
      (node (ref "R19") (pin "2") (pinfunction "2_2") (pintype "passive"))
      (node (ref "R20") (pin "2") (pinfunction "2_2") (pintype "passive"))
      (node (ref "R21") (pin "2") (pinfunction "2_2") (pintype "passive"))
      (node (ref "R22") (pin "2") (pinfunction "2_2") (pintype "passive"))
      (node (ref "R23") (pin "2") (pinfunction "2_2") (pintype "passive"))
      (node (ref "R25") (pin "1") (pinfunction "TOP_1") (pintype "passive"))
      (node (ref "R31") (pin "2") (pinfunction "2_2") (pintype "passive"))
      (node (ref "R34") (pin "2") (pinfunction "2_2") (pintype "passive"))
      (node (ref "R35") (pin "2") (pinfunction "2_2") (pintype "passive"))
      (node (ref "TP1") (pin "1") (pinfunction "1_1") (pintype "passive"))
      (node (ref "U1") (pin "15") (pinfunction "GND1_15") (pintype "power_in"))
      (node (ref "U1") (pin "9") (pinfunction "GND2_9") (pintype "power_in"))
      (node (ref "U2") (pin "15") (pinfunction "GND1_15") (pintype "power_in"))
      (node (ref "U2") (pin "9") (pinfunction "GND2_9") (pintype "power_in"))
      (node (ref "U3") (pin "8") (pinfunction "GND_8") (pintype "power_in"))
      (node (ref "U4") (pin "15") (pinfunction "GND1_15") (pintype "power_in"))
      (node (ref "U4") (pin "9") (pinfunction "GND2_9") (pintype "power_in"))
      (node (ref "U5") (pin "5") (pinfunction "GND_5") (pintype "power_in"))
      (node (ref "U6") (pin "4") (pinfunction "V-_4") (pintype "power_in"))
    )
    (net (code "35") (name "Net-(P2-Pad1)") (class "Default")
      (node (ref "P2") (pin "1") (pinfunction "1_1") (pintype "passive"))
      (node (ref "P2") (pin "2") (pinfunction "2_2") (pintype "passive"))
      (node (ref "R5") (pin "2") (pinfunction "2_2") (pintype "passive"))
    )
    (net (code "36") (name "Net-(P2-Pad3)") (class "Default")
      (node (ref "P2") (pin "3") (pinfunction "3_3") (pintype "passive"))
      (node (ref "P2") (pin "4") (pinfunction "4_4") (pintype "passive"))
      (node (ref "R4") (pin "2") (pinfunction "2_2") (pintype "passive"))
    )
    (net (code "37") (name "Net-(P2-Pad5)") (class "Default")
      (node (ref "P2") (pin "5") (pinfunction "5_5") (pintype "passive"))
      (node (ref "P2") (pin "6") (pinfunction "6_6") (pintype "passive"))
      (node (ref "R3") (pin "2") (pinfunction "2_2") (pintype "passive"))
    )
    (net (code "38") (name "Net-(P2-Pad7)") (class "Default")
      (node (ref "P2") (pin "7") (pinfunction "7_7") (pintype "passive"))
      (node (ref "P2") (pin "8") (pinfunction "8_8") (pintype "passive"))
      (node (ref "R2") (pin "2") (pinfunction "2_2") (pintype "passive"))
    )
    (net (code "39") (name "Net-(P2-Pad10)") (class "Default")
      (node (ref "P2") (pin "10") (pinfunction "10_10") (pintype "passive"))
      (node (ref "P2") (pin "9") (pinfunction "9_9") (pintype "passive"))
      (node (ref "R1") (pin "2") (pinfunction "2_2") (pintype "passive"))
    )
    (net (code "40") (name "Net-(P2-Pad11)") (class "Default")
      (node (ref "P2") (pin "11") (pinfunction "11_11") (pintype "passive"))
      (node (ref "P2") (pin "12") (pinfunction "12_12") (pintype "passive"))
      (node (ref "R6") (pin "2") (pinfunction "2_2") (pintype "passive"))
    )
    (net (code "41") (name "Net-(P4-Pad2)") (class "Default")
      (node (ref "P4") (pin "2") (pinfunction "2_2") (pintype "passive"))
      (node (ref "P5") (pin "1") (pinfunction "1_1") (pintype "passive"))
    )
    (net (code "42") (name "Net-(P4-Pad3)") (class "Default")
      (node (ref "P4") (pin "3") (pinfunction "3_3") (pintype "passive"))
      (node (ref "R32") (pin "2") (pinfunction "2_2") (pintype "passive"))
    )
    (net (code "43") (name "Net-(Q1-B)") (class "Default")
      (node (ref "Q1") (pin "2") (pinfunction "B_2") (pintype "passive"))
      (node (ref "R32") (pin "1") (pinfunction "1_1") (pintype "passive"))
      (node (ref "R34") (pin "1") (pinfunction "1_1") (pintype "passive"))
    )
    (net (code "44") (name "Net-(Q1-E)") (class "Default")
      (node (ref "Q1") (pin "3") (pinfunction "E_3") (pintype "passive"))
      (node (ref "R33") (pin "2") (pinfunction "2_2") (pintype "passive"))
      (node (ref "R35") (pin "1") (pinfunction "1_1") (pintype "passive"))
    )
    (net (code "45") (name "Net-(Q2-G)") (class "Default")
      (node (ref "Q2") (pin "1") (pinfunction "G_1") (pintype "passive"))
      (node (ref "R33") (pin "1") (pinfunction "1_1") (pintype "passive"))
    )
    (net (code "46") (name "Net-(R25-TAP)") (class "Default")
      (node (ref "R25") (pin "2") (pinfunction "TAP_2") (pintype "passive"))
      (node (ref "R26") (pin "1") (pinfunction "1_1") (pintype "passive"))
      (node (ref "TP15") (pin "1") (pinfunction "1_1") (pintype "passive"))
    )
    (net (code "47") (name "Net-(R26-Pad2)") (class "Default")
      (node (ref "R26") (pin "2") (pinfunction "2_2") (pintype "passive"))
      (node (ref "R27") (pin "2") (pinfunction "2_2") (pintype "passive"))
    )
    (net (code "48") (name "Net-(R28-Pad2)") (class "Default")
      (node (ref "R28") (pin "2") (pinfunction "2_2") (pintype "passive"))
      (node (ref "R29") (pin "2") (pinfunction "2_2") (pintype "passive"))
    )
    (net (code "49") (name "Net-(U1-DIR)") (class "Default")
      (node (ref "R8") (pin "1") (pinfunction "1_1") (pintype "passive"))
      (node (ref "U1") (pin "8") (pinfunction "DIR_8") (pintype "input"))
    )
    (net (code "50") (name "Net-(U1-MS1)") (class "Default")
      (node (ref "R14") (pin "1") (pinfunction "1_1") (pintype "passive"))
      (node (ref "U1") (pin "2") (pinfunction "MS1_2") (pintype "input"))
      (node (ref "U2") (pin "2") (pinfunction "MS1_2") (pintype "input"))
      (node (ref "U3") (pin "15") (pinfunction "QA_15") (pintype "output"))
    )
    (net (code "51") (name "Net-(U1-MS2)") (class "Default")
      (node (ref "R21") (pin "1") (pinfunction "1_1") (pintype "passive"))
      (node (ref "U1") (pin "3") (pinfunction "MS2_3") (pintype "input"))
      (node (ref "U2") (pin "3") (pinfunction "MS2_3") (pintype "input"))
      (node (ref "U3") (pin "1") (pinfunction "QB_1") (pintype "output"))
    )
    (net (code "52") (name "Net-(U1-MS3)") (class "Default")
      (node (ref "R15") (pin "1") (pinfunction "1_1") (pintype "passive"))
      (node (ref "U1") (pin "4") (pinfunction "MS3_4") (pintype "input"))
      (node (ref "U2") (pin "4") (pinfunction "MS3_4") (pintype "input"))
      (node (ref "U3") (pin "2") (pinfunction "QC_2") (pintype "output"))
    )
    (net (code "53") (name "Net-(U1-STEP)") (class "Default")
      (node (ref "R7") (pin "1") (pinfunction "1_1") (pintype "passive"))
      (node (ref "U1") (pin "7") (pinfunction "STEP_7") (pintype "input"))
    )
    (net (code "54") (name "Net-(U2-DIR)") (class "Default")
      (node (ref "R10") (pin "1") (pinfunction "1_1") (pintype "passive"))
      (node (ref "U2") (pin "8") (pinfunction "DIR_8") (pintype "input"))
    )
    (net (code "55") (name "Net-(U2-STEP)") (class "Default")
      (node (ref "R9") (pin "1") (pinfunction "1_1") (pintype "passive"))
      (node (ref "U2") (pin "7") (pinfunction "STEP_7") (pintype "input"))
    )
    (net (code "56") (name "Net-(U3-QD)") (class "Default")
      (node (ref "R22") (pin "1") (pinfunction "1_1") (pintype "passive"))
      (node (ref "U3") (pin "3") (pinfunction "QD_3") (pintype "output"))
      (node (ref "U4") (pin "2") (pinfunction "MS1_2") (pintype "input"))
    )
    (net (code "57") (name "Net-(U3-QE)") (class "Default")
      (node (ref "R16") (pin "1") (pinfunction "1_1") (pintype "passive"))
      (node (ref "U3") (pin "4") (pinfunction "QE_4") (pintype "output"))
      (node (ref "U4") (pin "3") (pinfunction "MS2_3") (pintype "input"))
    )
    (net (code "58") (name "Net-(U3-QF)") (class "Default")
      (node (ref "R23") (pin "1") (pinfunction "1_1") (pintype "passive"))
      (node (ref "U3") (pin "5") (pinfunction "QF_5") (pintype "output"))
      (node (ref "U4") (pin "4") (pinfunction "MS3_4") (pintype "input"))
    )
    (net (code "59") (name "Net-(U4-DIR)") (class "Default")
      (node (ref "R17") (pin "1") (pinfunction "1_1") (pintype "passive"))
      (node (ref "U4") (pin "8") (pinfunction "DIR_8") (pintype "input"))
    )
    (net (code "60") (name "Net-(U4-STEP)") (class "Default")
      (node (ref "R13") (pin "1") (pinfunction "1_1") (pintype "passive"))
      (node (ref "U4") (pin "7") (pinfunction "STEP_7") (pintype "input"))
    )
    (net (code "61") (name "Net-(U5-FILTER)") (class "Default")
      (node (ref "C6") (pin "2") (pinfunction "2_2") (pintype "passive"))
      (node (ref "U5") (pin "6") (pinfunction "FILTER_6") (pintype "input"))
    )
    (net (code "62") (name "Net-(U5-VIOUT)") (class "Default")
      (node (ref "R28") (pin "1") (pinfunction "1_1") (pintype "passive"))
      (node (ref "U5") (pin "7") (pinfunction "VIOUT_7") (pintype "output"))
    )
    (net (code "63") (name "Net-(U6-IN+)") (class "Default")
      (node (ref "R29") (pin "1") (pinfunction "1_1") (pintype "passive"))
      (node (ref "R31") (pin "1") (pinfunction "1_1") (pintype "passive"))
      (node (ref "U6") (pin "3") (pinfunction "IN+_3") (pintype "input"))
    )
    (net (code "64") (name "Net-(U6-IN-)") (class "Default")
      (node (ref "R24") (pin "1") (pinfunction "1_1") (pintype "passive"))
      (node (ref "R27") (pin "1") (pinfunction "1_1") (pintype "passive"))
      (node (ref "U6") (pin "2") (pinfunction "IN-_2") (pintype "input"))
    )
    (net (code "65") (name "Net-(U6-OUT)") (class "Default")
      (node (ref "R24") (pin "2") (pinfunction "2_2") (pintype "passive"))
      (node (ref "R30") (pin "1") (pinfunction "1_1") (pintype "passive"))
      (node (ref "U6") (pin "1") (pinfunction "OUT_1") (pintype "output"))
    )
    (net (code "66") (name "VCC") (class "Default")
      (node (ref "C8") (pin "1") (pinfunction "1_1") (pintype "passive"))
      (node (ref "D1") (pin "2") (pinfunction "K_2") (pintype "passive"))
      (node (ref "P3") (pin "1") (pinfunction "1_1") (pintype "passive"))
      (node (ref "P6") (pin "2") (pinfunction "2_2") (pintype "passive"))
    )
    (net (code "67") (name "Vin") (class "Default")
      (node (ref "C9") (pin "2") (pinfunction "2_2") (pintype "passive"))
      (node (ref "IC1") (pin "3") (pinfunction "Vin_3") (pintype "passive"))
      (node (ref "P8") (pin "1") (pinfunction "1_1") (pintype "passive"))
    )
    (net (code "68") (name "unconnected-(U1-EN-Pad1)") (class "Default")
      (node (ref "U1") (pin "1") (pinfunction "EN_1") (pintype "input+no_connect"))
    )
    (net (code "69") (name "unconnected-(U1-RST-Pad5)") (class "Default")
      (node (ref "U1") (pin "5") (pinfunction "RST_5") (pintype "input+no_connect"))
    )
    (net (code "70") (name "unconnected-(U1-SLP-Pad6)") (class "Default")
      (node (ref "U1") (pin "6") (pinfunction "SLP_6") (pintype "input+no_connect"))
    )
    (net (code "71") (name "unconnected-(U2-EN-Pad1)") (class "Default")
      (node (ref "U2") (pin "1") (pinfunction "EN_1") (pintype "input+no_connect"))
    )
    (net (code "72") (name "unconnected-(U2-RST-Pad5)") (class "Default")
      (node (ref "U2") (pin "5") (pinfunction "RST_5") (pintype "input+no_connect"))
    )
    (net (code "73") (name "unconnected-(U2-SLP-Pad6)") (class "Default")
      (node (ref "U2") (pin "6") (pinfunction "SLP_6") (pintype "input+no_connect"))
    )
    (net (code "74") (name "unconnected-(U3-QG-Pad6)") (class "Default")
      (node (ref "U3") (pin "6") (pinfunction "QG_6") (pintype "output"))
    )
    (net (code "75") (name "unconnected-(U3-QH*-Pad9)") (class "Default")
      (node (ref "U3") (pin "9") (pinfunction "QH*_9") (pintype "output"))
    )
    (net (code "76") (name "unconnected-(U3-QH-Pad7)") (class "Default")
      (node (ref "U3") (pin "7") (pinfunction "QH_7") (pintype "output"))
    )
    (net (code "77") (name "unconnected-(U4-EN-Pad1)") (class "Default")
      (node (ref "U4") (pin "1") (pinfunction "EN_1") (pintype "input+no_connect"))
    )
    (net (code "78") (name "unconnected-(U4-RST-Pad5)") (class "Default")
      (node (ref "U4") (pin "5") (pinfunction "RST_5") (pintype "input+no_connect"))
    )
    (net (code "79") (name "unconnected-(U4-SLP-Pad6)") (class "Default")
      (node (ref "U4") (pin "6") (pinfunction "SLP_6") (pintype "input+no_connect"))
    )
  )
)
